# 10_-_PERIPHERALS_C.net
KiCad netlist of a schematic drawn in Altium Designer
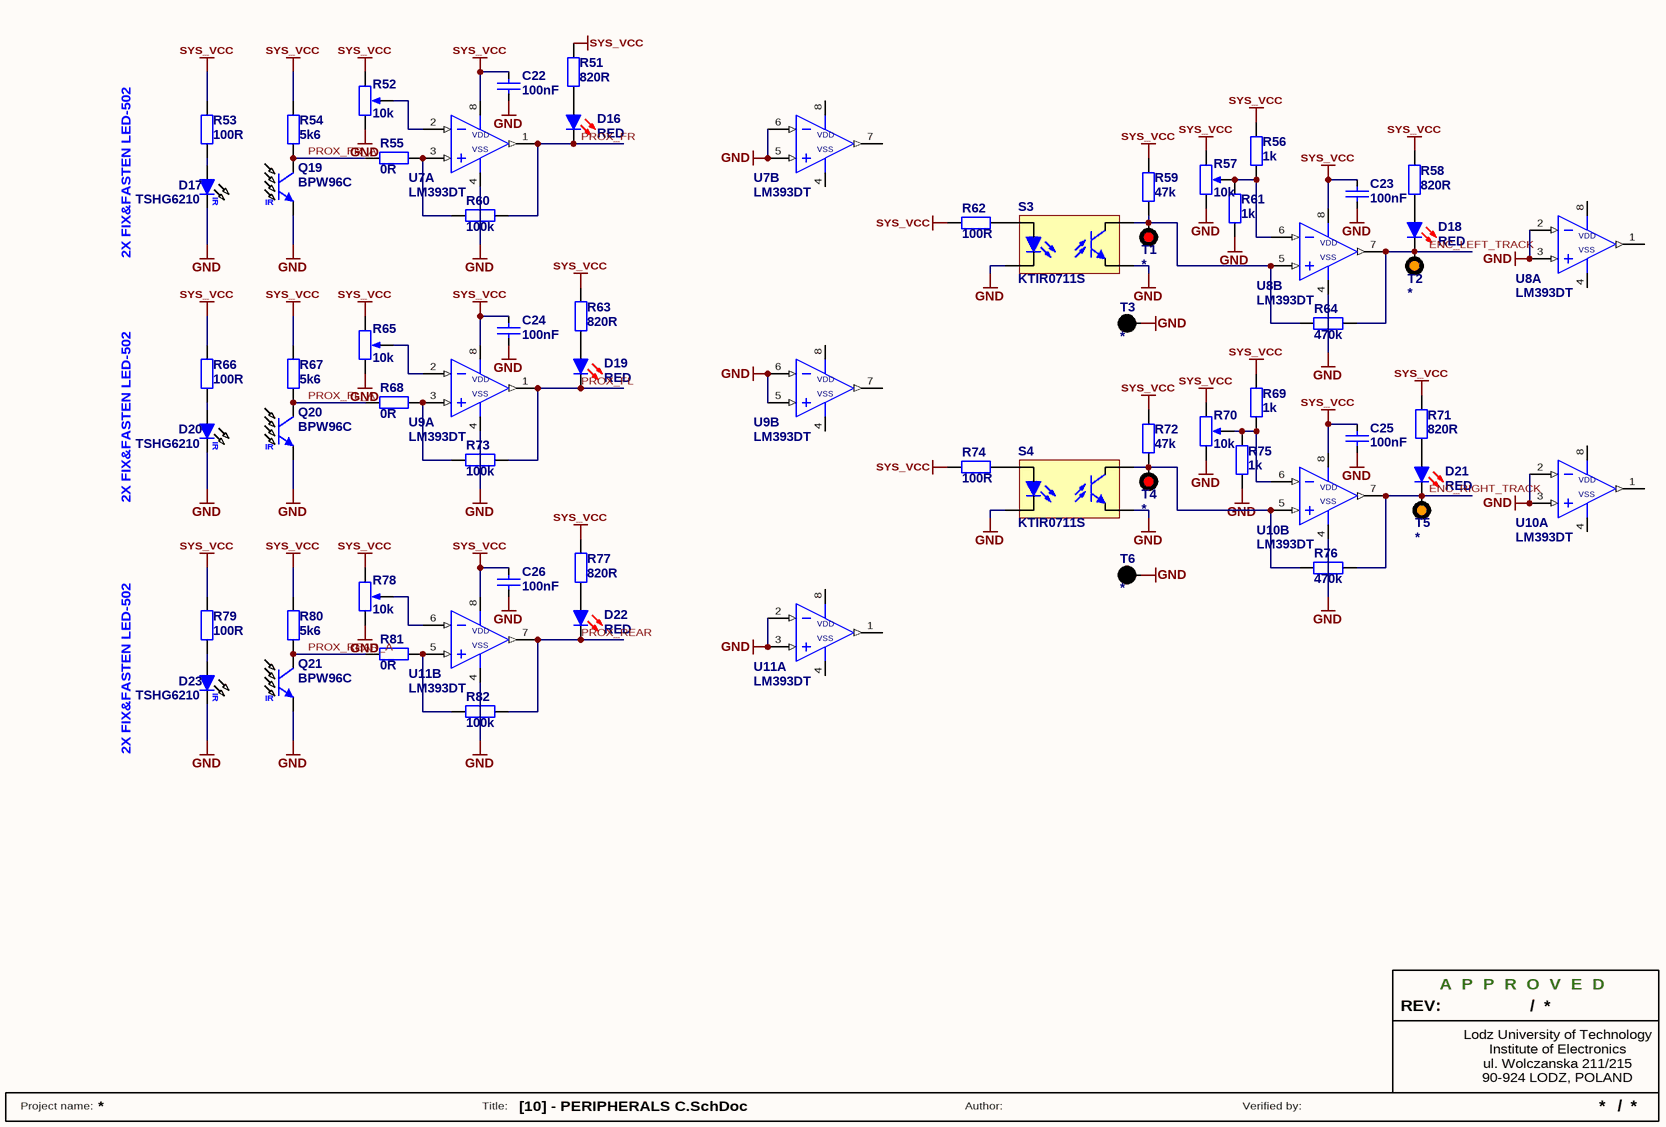
[diagram p0: [10] - PERIPHERALS C.SchDoc]

(export (version "E")
  (design (tool "Eeschema 10.0.6"))
  (components
    (comp (ref "C22")
      (value "100nF")
      (footprint "C0805")
      (description "Capacitor")
      (libsource (lib "capacitors") (part "Cap"))
    )
    (comp (ref "C23")
      (value "100nF")
      (footprint "C0805")
      (description "Capacitor")
      (libsource (lib "capacitors") (part "Cap"))
    )
    (comp (ref "C24")
      (value "100nF")
      (footprint "C0805")
      (description "Capacitor")
      (libsource (lib "capacitors") (part "Cap"))
    )
    (comp (ref "C25")
      (value "100nF")
      (footprint "C0805")
      (description "Capacitor")
      (libsource (lib "capacitors") (part "Cap"))
    )
    (comp (ref "C26")
      (value "100nF")
      (footprint "C0805")
      (description "Capacitor")
      (libsource (lib "capacitors") (part "Cap"))
    )
    (comp (ref "D16")
      (value "RED")
      (footprint "LED0805R")
      (description "RED LED")
      (libsource (lib "leds") (part "LED_RED"))
    )
    (comp (ref "D17")
      (value "TSHG6210")
      (footprint "LED-502")
      (description "IR transmitter; 5mm; 850nm; transparent; 230mW; 10°; THT; 1.5÷1.8V")
      (libsource (lib "leds") (part "TSHG6210"))
    )
    (comp (ref "D18")
      (value "RED")
      (footprint "LED0805R")
      (description "RED LED")
      (libsource (lib "leds") (part "LED_RED"))
    )
    (comp (ref "D19")
      (value "RED")
      (footprint "LED0805R")
      (description "RED LED")
      (libsource (lib "leds") (part "LED_RED"))
    )
    (comp (ref "D20")
      (value "TSHG6210")
      (footprint "LED-502")
      (description "IR transmitter; 5mm; 850nm; transparent; 230mW; 10°; THT; 1.5÷1.8V")
      (libsource (lib "leds") (part "TSHG6210"))
    )
    (comp (ref "D21")
      (value "RED")
      (footprint "LED0805R")
      (description "RED LED")
      (libsource (lib "leds") (part "LED_RED"))
    )
    (comp (ref "D22")
      (value "RED")
      (footprint "LED0805R")
      (description "RED LED")
      (libsource (lib "leds") (part "LED_RED"))
    )
    (comp (ref "D23")
      (value "TSHG6210")
      (footprint "LED-502")
      (description "IR transmitter; 5mm; 850nm; transparent; 230mW; 10°; THT; 1.5÷1.8V")
      (libsource (lib "leds") (part "TSHG6210"))
    )
    (comp (ref "Q19")
      (value "BPW96C")
      (footprint "LED-502")
      (description "Phototransistor; λp max:850nm; 70V; 20°; Lens: transparent; Ø:5mm")
      (libsource (lib "photoelements") (part "BPW96C"))
    )
    (comp (ref "Q20")
      (value "BPW96C")
      (footprint "LED-502")
      (description "Phototransistor; λp max:850nm; 70V; 20°; Lens: transparent; Ø:5mm")
      (libsource (lib "photoelements") (part "BPW96C"))
    )
    (comp (ref "Q21")
      (value "BPW96C")
      (footprint "LED-502")
      (description "Phototransistor; λp max:850nm; 70V; 20°; Lens: transparent; Ø:5mm")
      (libsource (lib "photoelements") (part "BPW96C"))
    )
    (comp (ref "R51")
      (value "820R")
      (footprint "R0805")
      (description "Resistor")
      (libsource (lib "resistors") (part "Res"))
    )
    (comp (ref "R52")
      (value "10k")
      (footprint "3305SMD")
      (description "3305SMD-10K")
      (libsource (lib "resistors") (part "3305SMD-10K"))
    )
    (comp (ref "R53")
      (value "100R")
      (footprint "R0805")
      (description "Resistor")
      (libsource (lib "resistors") (part "Res"))
    )
    (comp (ref "R54")
      (value "5k6")
      (footprint "R0805")
      (description "Resistor")
      (libsource (lib "resistors") (part "Res"))
    )
    (comp (ref "R55")
      (value "0R")
      (footprint "R0805")
      (description "Resistor")
      (libsource (lib "") (part "Res_1"))
    )
    (comp (ref "R56")
      (value "1k")
      (footprint "R0805")
      (description "Resistor")
      (libsource (lib "resistors") (part "Res"))
    )
    (comp (ref "R57")
      (value "10k")
      (footprint "3305SMD")
      (description "3305SMD-10K")
      (libsource (lib "resistors") (part "3305SMD-10K"))
    )
    (comp (ref "R58")
      (value "820R")
      (footprint "R0805")
      (description "Resistor")
      (libsource (lib "resistors") (part "Res"))
    )
    (comp (ref "R59")
      (value "47k")
      (footprint "R0805")
      (description "Resistor")
      (libsource (lib "") (part "Res_3"))
    )
    (comp (ref "R60")
      (value "100k")
      (footprint "R0805")
      (description "Resistor")
      (libsource (lib "") (part "Res_1"))
    )
    (comp (ref "R61")
      (value "1k")
      (footprint "R0805")
      (description "Resistor")
      (libsource (lib "resistors") (part "Res"))
    )
    (comp (ref "R62")
      (value "100R")
      (footprint "R0805")
      (description "Resistor")
      (libsource (lib "") (part "Res_2"))
    )
    (comp (ref "R63")
      (value "820R")
      (footprint "R0805")
      (description "Resistor")
      (libsource (lib "resistors") (part "Res"))
    )
    (comp (ref "R64")
      (value "470k")
      (footprint "R0805")
      (description "Resistor")
      (libsource (lib "") (part "Res_1"))
    )
    (comp (ref "R65")
      (value "10k")
      (footprint "3305SMD")
      (description "3305SMD-10K")
      (libsource (lib "resistors") (part "3305SMD-10K"))
    )
    (comp (ref "R66")
      (value "100R")
      (footprint "R0805")
      (description "Resistor")
      (libsource (lib "resistors") (part "Res"))
    )
    (comp (ref "R67")
      (value "5k6")
      (footprint "R0805")
      (description "Resistor")
      (libsource (lib "resistors") (part "Res"))
    )
    (comp (ref "R68")
      (value "0R")
      (footprint "R0805")
      (description "Resistor")
      (libsource (lib "") (part "Res_1"))
    )
    (comp (ref "R69")
      (value "1k")
      (footprint "R0805")
      (description "Resistor")
      (libsource (lib "resistors") (part "Res"))
    )
    (comp (ref "R70")
      (value "10k")
      (footprint "3305SMD")
      (description "3305SMD-10K")
      (libsource (lib "resistors") (part "3305SMD-10K"))
    )
    (comp (ref "R71")
      (value "820R")
      (footprint "R0805")
      (description "Resistor")
      (libsource (lib "resistors") (part "Res"))
    )
    (comp (ref "R72")
      (value "47k")
      (footprint "R0805")
      (description "Resistor")
      (libsource (lib "") (part "Res_3"))
    )
    (comp (ref "R73")
      (value "100k")
      (footprint "R0805")
      (description "Resistor")
      (libsource (lib "") (part "Res_1"))
    )
    (comp (ref "R74")
      (value "100R")
      (footprint "R0805")
      (description "Resistor")
      (libsource (lib "") (part "Res_2"))
    )
    (comp (ref "R75")
      (value "1k")
      (footprint "R0805")
      (description "Resistor")
      (libsource (lib "resistors") (part "Res"))
    )
    (comp (ref "R76")
      (value "470k")
      (footprint "R0805")
      (description "Resistor")
      (libsource (lib "") (part "Res_1"))
    )
    (comp (ref "R77")
      (value "820R")
      (footprint "R0805")
      (description "Resistor")
      (libsource (lib "resistors") (part "Res"))
    )
    (comp (ref "R78")
      (value "10k")
      (footprint "3305SMD")
      (description "3305SMD-10K")
      (libsource (lib "resistors") (part "3305SMD-10K"))
    )
    (comp (ref "R79")
      (value "100R")
      (footprint "R0805")
      (description "Resistor")
      (libsource (lib "resistors") (part "Res"))
    )
    (comp (ref "R80")
      (value "5k6")
      (footprint "R0805")
      (description "Resistor")
      (libsource (lib "resistors") (part "Res"))
    )
    (comp (ref "R81")
      (value "0R")
      (footprint "R0805")
      (description "Resistor")
      (libsource (lib "") (part "Res_1"))
    )
    (comp (ref "R82")
      (value "100k")
      (footprint "R0805")
      (description "Resistor")
      (libsource (lib "") (part "Res_1"))
    )
    (comp (ref "S3")
      (value "KTIR0711S")
      (footprint "KTIR0711S_wide_pads")
      (description "SUBMINIATURE, HIGH SENSITIVITY PHOTOINTERRUPTER")
      (libsource (lib "photoelectric_sensors") (part "KTIR0711S"))
    )
    (comp (ref "S4")
      (value "KTIR0711S")
      (footprint "KTIR0711S_wide_pads")
      (description "SUBMINIATURE, HIGH SENSITIVITY PHOTOINTERRUPTER")
      (libsource (lib "photoelectric_sensors") (part "KTIR0711S"))
    )
    (comp (ref "T1")
      (value "*")
      (footprint "Keystone_5000_RED")
      (description "Keystone 5000 Test Point (RED)")
      (libsource (lib "test_points") (part "Keystone 5000 Test Point"))
    )
    (comp (ref "T2")
      (value "*")
      (footprint "Keystone_5003_ORANGE")
      (description "Keystone 5003 Test Point (ORANGE)")
      (libsource (lib "test_points") (part "Keystone 5003 Test Point"))
    )
    (comp (ref "T3")
      (value "*")
      (footprint "Keystone_5001_BLACK")
      (description "Keystone 5001 Test Point (BLACK)")
      (libsource (lib "test_points") (part "Keystone 5001 Test Point"))
    )
    (comp (ref "T4")
      (value "*")
      (footprint "Keystone_5000_RED")
      (description "Keystone 5000 Test Point (RED)")
      (libsource (lib "test_points") (part "Keystone 5000 Test Point"))
    )
    (comp (ref "T5")
      (value "*")
      (footprint "Keystone_5003_ORANGE")
      (description "Keystone 5003 Test Point (ORANGE)")
      (libsource (lib "test_points") (part "Keystone 5003 Test Point"))
    )
    (comp (ref "T6")
      (value "*")
      (footprint "Keystone_5001_BLACK")
      (description "Keystone 5001 Test Point (BLACK)")
      (libsource (lib "test_points") (part "Keystone 5001 Test Point"))
    )
    (comp (ref "U7")
      (value "LM393DT")
      (footprint "SO8")
      (description "Low power dual voltage comparators")
      (libsource (lib "comparators") (part "LM393DT"))
    )
    (comp (ref "U8")
      (value "LM393DT")
      (footprint "SO8")
      (description "Low power dual voltage comparators")
      (libsource (lib "comparators") (part "LM393DT"))
    )
    (comp (ref "U9")
      (value "LM393DT")
      (footprint "SO8")
      (description "Low power dual voltage comparators")
      (libsource (lib "comparators") (part "LM393DT"))
    )
    (comp (ref "U10")
      (value "LM393DT")
      (footprint "SO8")
      (description "Low power dual voltage comparators")
      (libsource (lib "comparators") (part "LM393DT"))
    )
    (comp (ref "U11")
      (value "LM393DT")
      (footprint "SO8")
      (description "Low power dual voltage comparators")
      (libsource (lib "comparators") (part "LM393DT"))
    )
  )
  (nets
    (net (code "1") (name "/ENC_LEFT_TRACK") (class "Default")
      (node (ref "D18") (pin "2") (pinfunction "K_2") (pintype "passive"))
      (node (ref "R64") (pin "2") (pinfunction "2_2") (pintype "passive"))
      (node (ref "T2") (pin "0") (pinfunction "0_0") (pintype "passive"))
      (node (ref "U8") (pin "7") (pinfunction "OUT_7") (pintype "output"))
    )
    (net (code "2") (name "/ENC_RIGHT_TRACK") (class "Default")
      (node (ref "D21") (pin "2") (pinfunction "K_2") (pintype "passive"))
      (node (ref "R76") (pin "2") (pinfunction "2_2") (pintype "passive"))
      (node (ref "T5") (pin "0") (pinfunction "0_0") (pintype "passive"))
      (node (ref "U10") (pin "7") (pinfunction "OUT_7") (pintype "output"))
    )
    (net (code "3") (name "/PROX_FL") (class "Default")
      (node (ref "D19") (pin "2") (pinfunction "K_2") (pintype "passive"))
      (node (ref "R73") (pin "2") (pinfunction "2_2") (pintype "passive"))
      (node (ref "U9") (pin "1") (pinfunction "OUT_1") (pintype "output"))
    )
    (net (code "4") (name "/PROX_FL_A") (class "Default")
      (node (ref "Q20") (pin "2") (pinfunction "C_2") (pintype "passive"))
      (node (ref "R67") (pin "2") (pinfunction "2_2") (pintype "passive"))
      (node (ref "R68") (pin "1") (pinfunction "1_1") (pintype "passive"))
    )
    (net (code "5") (name "/PROX_FR") (class "Default")
      (node (ref "D16") (pin "2") (pinfunction "K_2") (pintype "passive"))
      (node (ref "R60") (pin "2") (pinfunction "2_2") (pintype "passive"))
      (node (ref "U7") (pin "1") (pinfunction "OUT_1") (pintype "output"))
    )
    (net (code "6") (name "/PROX_FR_A") (class "Default")
      (node (ref "Q19") (pin "2") (pinfunction "C_2") (pintype "passive"))
      (node (ref "R54") (pin "2") (pinfunction "2_2") (pintype "passive"))
      (node (ref "R55") (pin "1") (pinfunction "1_1") (pintype "passive"))
    )
    (net (code "7") (name "/PROX_REAR") (class "Default")
      (node (ref "D22") (pin "2") (pinfunction "K_2") (pintype "passive"))
      (node (ref "R82") (pin "2") (pinfunction "2_2") (pintype "passive"))
      (node (ref "U11") (pin "7") (pinfunction "OUT_7") (pintype "output"))
    )
    (net (code "8") (name "/PROX_REAR_A") (class "Default")
      (node (ref "Q21") (pin "2") (pinfunction "C_2") (pintype "passive"))
      (node (ref "R80") (pin "2") (pinfunction "2_2") (pintype "passive"))
      (node (ref "R81") (pin "1") (pinfunction "1_1") (pintype "passive"))
    )
    (net (code "9") (name "GND") (class "Default")
      (node (ref "C22") (pin "2") (pinfunction "2_2") (pintype "passive"))
      (node (ref "C23") (pin "2") (pinfunction "2_2") (pintype "passive"))
      (node (ref "C24") (pin "2") (pinfunction "2_2") (pintype "passive"))
      (node (ref "C25") (pin "2") (pinfunction "2_2") (pintype "passive"))
      (node (ref "C26") (pin "2") (pinfunction "2_2") (pintype "passive"))
      (node (ref "D17") (pin "2") (pinfunction "K_2") (pintype "passive"))
      (node (ref "D20") (pin "2") (pinfunction "K_2") (pintype "passive"))
      (node (ref "D23") (pin "2") (pinfunction "K_2") (pintype "passive"))
      (node (ref "Q19") (pin "1") (pinfunction "E_1") (pintype "passive"))
      (node (ref "Q20") (pin "1") (pinfunction "E_1") (pintype "passive"))
      (node (ref "Q21") (pin "1") (pinfunction "E_1") (pintype "passive"))
      (node (ref "R52") (pin "2") (pinfunction "BOT_2") (pintype "passive"))
      (node (ref "R57") (pin "2") (pinfunction "BOT_2") (pintype "passive"))
      (node (ref "R61") (pin "2") (pinfunction "2_2") (pintype "passive"))
      (node (ref "R65") (pin "2") (pinfunction "BOT_2") (pintype "passive"))
      (node (ref "R70") (pin "2") (pinfunction "BOT_2") (pintype "passive"))
      (node (ref "R75") (pin "2") (pinfunction "2_2") (pintype "passive"))
      (node (ref "R78") (pin "2") (pinfunction "BOT_2") (pintype "passive"))
      (node (ref "S3") (pin "2") (pinfunction "E_2") (pintype "passive"))
      (node (ref "S3") (pin "4") (pinfunction "K_4") (pintype "passive"))
      (node (ref "S4") (pin "2") (pinfunction "E_2") (pintype "passive"))
      (node (ref "S4") (pin "4") (pinfunction "K_4") (pintype "passive"))
      (node (ref "T3") (pin "0") (pinfunction "0_0") (pintype "passive"))
      (node (ref "T6") (pin "0") (pinfunction "0_0") (pintype "passive"))
      (node (ref "U10") (pin "2") (pinfunction "IN-_2") (pintype "input"))
      (node (ref "U10") (pin "3") (pinfunction "IN+_3") (pintype "input"))
      (node (ref "U10") (pin "4") (pinfunction "GND_4") (pintype "power_in"))
      (node (ref "U11") (pin "2") (pinfunction "IN-_2") (pintype "input"))
      (node (ref "U11") (pin "3") (pinfunction "IN+_3") (pintype "input"))
      (node (ref "U11") (pin "4") (pinfunction "GND_4") (pintype "power_in"))
      (node (ref "U7") (pin "4") (pinfunction "GND_4") (pintype "power_in"))
      (node (ref "U7") (pin "5") (pinfunction "IN+_5") (pintype "input"))
      (node (ref "U7") (pin "6") (pinfunction "IN-_6") (pintype "input"))
      (node (ref "U8") (pin "2") (pinfunction "IN-_2") (pintype "input"))
      (node (ref "U8") (pin "3") (pinfunction "IN+_3") (pintype "input"))
      (node (ref "U8") (pin "4") (pinfunction "GND_4") (pintype "power_in"))
      (node (ref "U9") (pin "4") (pinfunction "GND_4") (pintype "power_in"))
      (node (ref "U9") (pin "5") (pinfunction "IN+_5") (pintype "input"))
      (node (ref "U9") (pin "6") (pinfunction "IN-_6") (pintype "input"))
    )
    (net (code "10") (name "Net-(D16-A)") (class "Default")
      (node (ref "D16") (pin "1") (pinfunction "A_1") (pintype "passive"))
      (node (ref "R51") (pin "2") (pinfunction "2_2") (pintype "passive"))
    )
    (net (code "11") (name "Net-(D17-A)") (class "Default")
      (node (ref "D17") (pin "1") (pinfunction "A_1") (pintype "passive"))
      (node (ref "R53") (pin "2") (pinfunction "2_2") (pintype "passive"))
    )
    (net (code "12") (name "Net-(D18-A)") (class "Default")
      (node (ref "D18") (pin "1") (pinfunction "A_1") (pintype "passive"))
      (node (ref "R58") (pin "2") (pinfunction "2_2") (pintype "passive"))
    )
    (net (code "13") (name "Net-(D19-A)") (class "Default")
      (node (ref "D19") (pin "1") (pinfunction "A_1") (pintype "passive"))
      (node (ref "R63") (pin "2") (pinfunction "2_2") (pintype "passive"))
    )
    (net (code "14") (name "Net-(D20-A)") (class "Default")
      (node (ref "D20") (pin "1") (pinfunction "A_1") (pintype "passive"))
      (node (ref "R66") (pin "2") (pinfunction "2_2") (pintype "passive"))
    )
    (net (code "15") (name "Net-(D21-A)") (class "Default")
      (node (ref "D21") (pin "1") (pinfunction "A_1") (pintype "passive"))
      (node (ref "R71") (pin "2") (pinfunction "2_2") (pintype "passive"))
    )
    (net (code "16") (name "Net-(D22-A)") (class "Default")
      (node (ref "D22") (pin "1") (pinfunction "A_1") (pintype "passive"))
      (node (ref "R77") (pin "2") (pinfunction "2_2") (pintype "passive"))
    )
    (net (code "17") (name "Net-(D23-A)") (class "Default")
      (node (ref "D23") (pin "1") (pinfunction "A_1") (pintype "passive"))
      (node (ref "R79") (pin "2") (pinfunction "2_2") (pintype "passive"))
    )
    (net (code "18") (name "Net-(R52-TAP)") (class "Default")
      (node (ref "R52") (pin "3") (pinfunction "TAP_3") (pintype "passive"))
      (node (ref "U7") (pin "2") (pinfunction "IN-_2") (pintype "input"))
    )
    (net (code "19") (name "Net-(R57-TAP)") (class "Default")
      (node (ref "R56") (pin "2") (pinfunction "2_2") (pintype "passive"))
      (node (ref "R57") (pin "3") (pinfunction "TAP_3") (pintype "passive"))
      (node (ref "R61") (pin "1") (pinfunction "1_1") (pintype "passive"))
      (node (ref "U8") (pin "6") (pinfunction "IN-_6") (pintype "input"))
    )
    (net (code "20") (name "Net-(R65-TAP)") (class "Default")
      (node (ref "R65") (pin "3") (pinfunction "TAP_3") (pintype "passive"))
      (node (ref "U9") (pin "2") (pinfunction "IN-_2") (pintype "input"))
    )
    (net (code "21") (name "Net-(R70-TAP)") (class "Default")
      (node (ref "R69") (pin "2") (pinfunction "2_2") (pintype "passive"))
      (node (ref "R70") (pin "3") (pinfunction "TAP_3") (pintype "passive"))
      (node (ref "R75") (pin "1") (pinfunction "1_1") (pintype "passive"))
      (node (ref "U10") (pin "6") (pinfunction "IN-_6") (pintype "input"))
    )
    (net (code "22") (name "Net-(R78-TAP)") (class "Default")
      (node (ref "R78") (pin "3") (pinfunction "TAP_3") (pintype "passive"))
      (node (ref "U11") (pin "6") (pinfunction "IN-_6") (pintype "input"))
    )
    (net (code "23") (name "Net-(S3-A)") (class "Default")
      (node (ref "R62") (pin "1") (pinfunction "1_1") (pintype "passive"))
      (node (ref "S3") (pin "1") (pinfunction "A_1") (pintype "passive"))
    )
    (net (code "24") (name "Net-(S3-C)") (class "Default")
      (node (ref "R59") (pin "1") (pinfunction "1_1") (pintype "passive"))
      (node (ref "R64") (pin "1") (pinfunction "1_1") (pintype "passive"))
      (node (ref "S3") (pin "3") (pinfunction "C_3") (pintype "passive"))
      (node (ref "T1") (pin "0") (pinfunction "0_0") (pintype "passive"))
      (node (ref "U8") (pin "5") (pinfunction "IN+_5") (pintype "input"))
    )
    (net (code "25") (name "Net-(S4-A)") (class "Default")
      (node (ref "R74") (pin "1") (pinfunction "1_1") (pintype "passive"))
      (node (ref "S4") (pin "1") (pinfunction "A_1") (pintype "passive"))
    )
    (net (code "26") (name "Net-(S4-C)") (class "Default")
      (node (ref "R72") (pin "1") (pinfunction "1_1") (pintype "passive"))
      (node (ref "R76") (pin "1") (pinfunction "1_1") (pintype "passive"))
      (node (ref "S4") (pin "3") (pinfunction "C_3") (pintype "passive"))
      (node (ref "T4") (pin "0") (pinfunction "0_0") (pintype "passive"))
      (node (ref "U10") (pin "5") (pinfunction "IN+_5") (pintype "input"))
    )
    (net (code "27") (name "Net-(U7A-IN+)") (class "Default")
      (node (ref "R55") (pin "2") (pinfunction "2_2") (pintype "passive"))
      (node (ref "R60") (pin "1") (pinfunction "1_1") (pintype "passive"))
      (node (ref "U7") (pin "3") (pinfunction "IN+_3") (pintype "input"))
    )
    (net (code "28") (name "Net-(U9A-IN+)") (class "Default")
      (node (ref "R68") (pin "2") (pinfunction "2_2") (pintype "passive"))
      (node (ref "R73") (pin "1") (pinfunction "1_1") (pintype "passive"))
      (node (ref "U9") (pin "3") (pinfunction "IN+_3") (pintype "input"))
    )
    (net (code "29") (name "Net-(U11B-IN+)") (class "Default")
      (node (ref "R81") (pin "2") (pinfunction "2_2") (pintype "passive"))
      (node (ref "R82") (pin "1") (pinfunction "1_1") (pintype "passive"))
      (node (ref "U11") (pin "5") (pinfunction "IN+_5") (pintype "input"))
    )
    (net (code "30") (name "SYS_VCC") (class "Default")
      (node (ref "C22") (pin "1") (pinfunction "1_1") (pintype "passive"))
      (node (ref "C23") (pin "1") (pinfunction "1_1") (pintype "passive"))
      (node (ref "C24") (pin "1") (pinfunction "1_1") (pintype "passive"))
      (node (ref "C25") (pin "1") (pinfunction "1_1") (pintype "passive"))
      (node (ref "C26") (pin "1") (pinfunction "1_1") (pintype "passive"))
      (node (ref "R51") (pin "1") (pinfunction "1_1") (pintype "passive"))
      (node (ref "R52") (pin "1") (pinfunction "TOP_1") (pintype "passive"))
      (node (ref "R53") (pin "1") (pinfunction "1_1") (pintype "passive"))
      (node (ref "R54") (pin "1") (pinfunction "1_1") (pintype "passive"))
      (node (ref "R56") (pin "1") (pinfunction "1_1") (pintype "passive"))
      (node (ref "R57") (pin "1") (pinfunction "TOP_1") (pintype "passive"))
      (node (ref "R58") (pin "1") (pinfunction "1_1") (pintype "passive"))
      (node (ref "R59") (pin "2") (pinfunction "2_2") (pintype "passive"))
      (node (ref "R62") (pin "2") (pinfunction "2_2") (pintype "passive"))
      (node (ref "R63") (pin "1") (pinfunction "1_1") (pintype "passive"))
      (node (ref "R65") (pin "1") (pinfunction "TOP_1") (pintype "passive"))
      (node (ref "R66") (pin "1") (pinfunction "1_1") (pintype "passive"))
      (node (ref "R67") (pin "1") (pinfunction "1_1") (pintype "passive"))
      (node (ref "R69") (pin "1") (pinfunction "1_1") (pintype "passive"))
      (node (ref "R70") (pin "1") (pinfunction "TOP_1") (pintype "passive"))
      (node (ref "R71") (pin "1") (pinfunction "1_1") (pintype "passive"))
      (node (ref "R72") (pin "2") (pinfunction "2_2") (pintype "passive"))
      (node (ref "R74") (pin "2") (pinfunction "2_2") (pintype "passive"))
      (node (ref "R77") (pin "1") (pinfunction "1_1") (pintype "passive"))
      (node (ref "R78") (pin "1") (pinfunction "TOP_1") (pintype "passive"))
      (node (ref "R79") (pin "1") (pinfunction "1_1") (pintype "passive"))
      (node (ref "R80") (pin "1") (pinfunction "1_1") (pintype "passive"))
      (node (ref "U10") (pin "8") (pinfunction "V+_8") (pintype "power_in"))
      (node (ref "U11") (pin "8") (pinfunction "V+_8") (pintype "power_in"))
      (node (ref "U7") (pin "8") (pinfunction "V+_8") (pintype "power_in"))
      (node (ref "U8") (pin "8") (pinfunction "V+_8") (pintype "power_in"))
      (node (ref "U9") (pin "8") (pinfunction "V+_8") (pintype "power_in"))
    )
    (net (code "31") (name "unconnected-(U7B-GND-Pad4)") (class "Default")
      (node (ref "U7") (pin "4") (pinfunction "GND_4") (pintype "power_in"))
    )
    (net (code "32") (name "unconnected-(U7B-OUT-Pad7)") (class "Default")
      (node (ref "U7") (pin "7") (pinfunction "OUT_7") (pintype "output"))
    )
    (net (code "33") (name "unconnected-(U7B-V+-Pad8)") (class "Default")
      (node (ref "U7") (pin "8") (pinfunction "V+_8") (pintype "power_in"))
    )
    (net (code "34") (name "unconnected-(U8A-GND-Pad4)") (class "Default")
      (node (ref "U8") (pin "4") (pinfunction "GND_4") (pintype "power_in"))
    )
    (net (code "35") (name "unconnected-(U8A-OUT-Pad1)") (class "Default")
      (node (ref "U8") (pin "1") (pinfunction "OUT_1") (pintype "output"))
    )
    (net (code "36") (name "unconnected-(U8A-V+-Pad8)") (class "Default")
      (node (ref "U8") (pin "8") (pinfunction "V+_8") (pintype "power_in"))
    )
    (net (code "37") (name "unconnected-(U9B-GND-Pad4)") (class "Default")
      (node (ref "U9") (pin "4") (pinfunction "GND_4") (pintype "power_in"))
    )
    (net (code "38") (name "unconnected-(U9B-OUT-Pad7)") (class "Default")
      (node (ref "U9") (pin "7") (pinfunction "OUT_7") (pintype "output"))
    )
    (net (code "39") (name "unconnected-(U9B-V+-Pad8)") (class "Default")
      (node (ref "U9") (pin "8") (pinfunction "V+_8") (pintype "power_in"))
    )
    (net (code "40") (name "unconnected-(U10A-GND-Pad4)") (class "Default")
      (node (ref "U10") (pin "4") (pinfunction "GND_4") (pintype "power_in"))
    )
    (net (code "41") (name "unconnected-(U10A-OUT-Pad1)") (class "Default")
      (node (ref "U10") (pin "1") (pinfunction "OUT_1") (pintype "output"))
    )
    (net (code "42") (name "unconnected-(U10A-V+-Pad8)") (class "Default")
      (node (ref "U10") (pin "8") (pinfunction "V+_8") (pintype "power_in"))
    )
    (net (code "43") (name "unconnected-(U11A-GND-Pad4)") (class "Default")
      (node (ref "U11") (pin "4") (pinfunction "GND_4") (pintype "power_in"))
    )
    (net (code "44") (name "unconnected-(U11A-OUT-Pad1)") (class "Default")
      (node (ref "U11") (pin "1") (pinfunction "OUT_1") (pintype "output"))
    )
    (net (code "45") (name "unconnected-(U11A-V+-Pad8)") (class "Default")
      (node (ref "U11") (pin "8") (pinfunction "V+_8") (pintype "power_in"))
    )
  )
)
